# Magnetic-Imaging-Tile.net
KiCad netlist of a schematic drawn in EAGLE
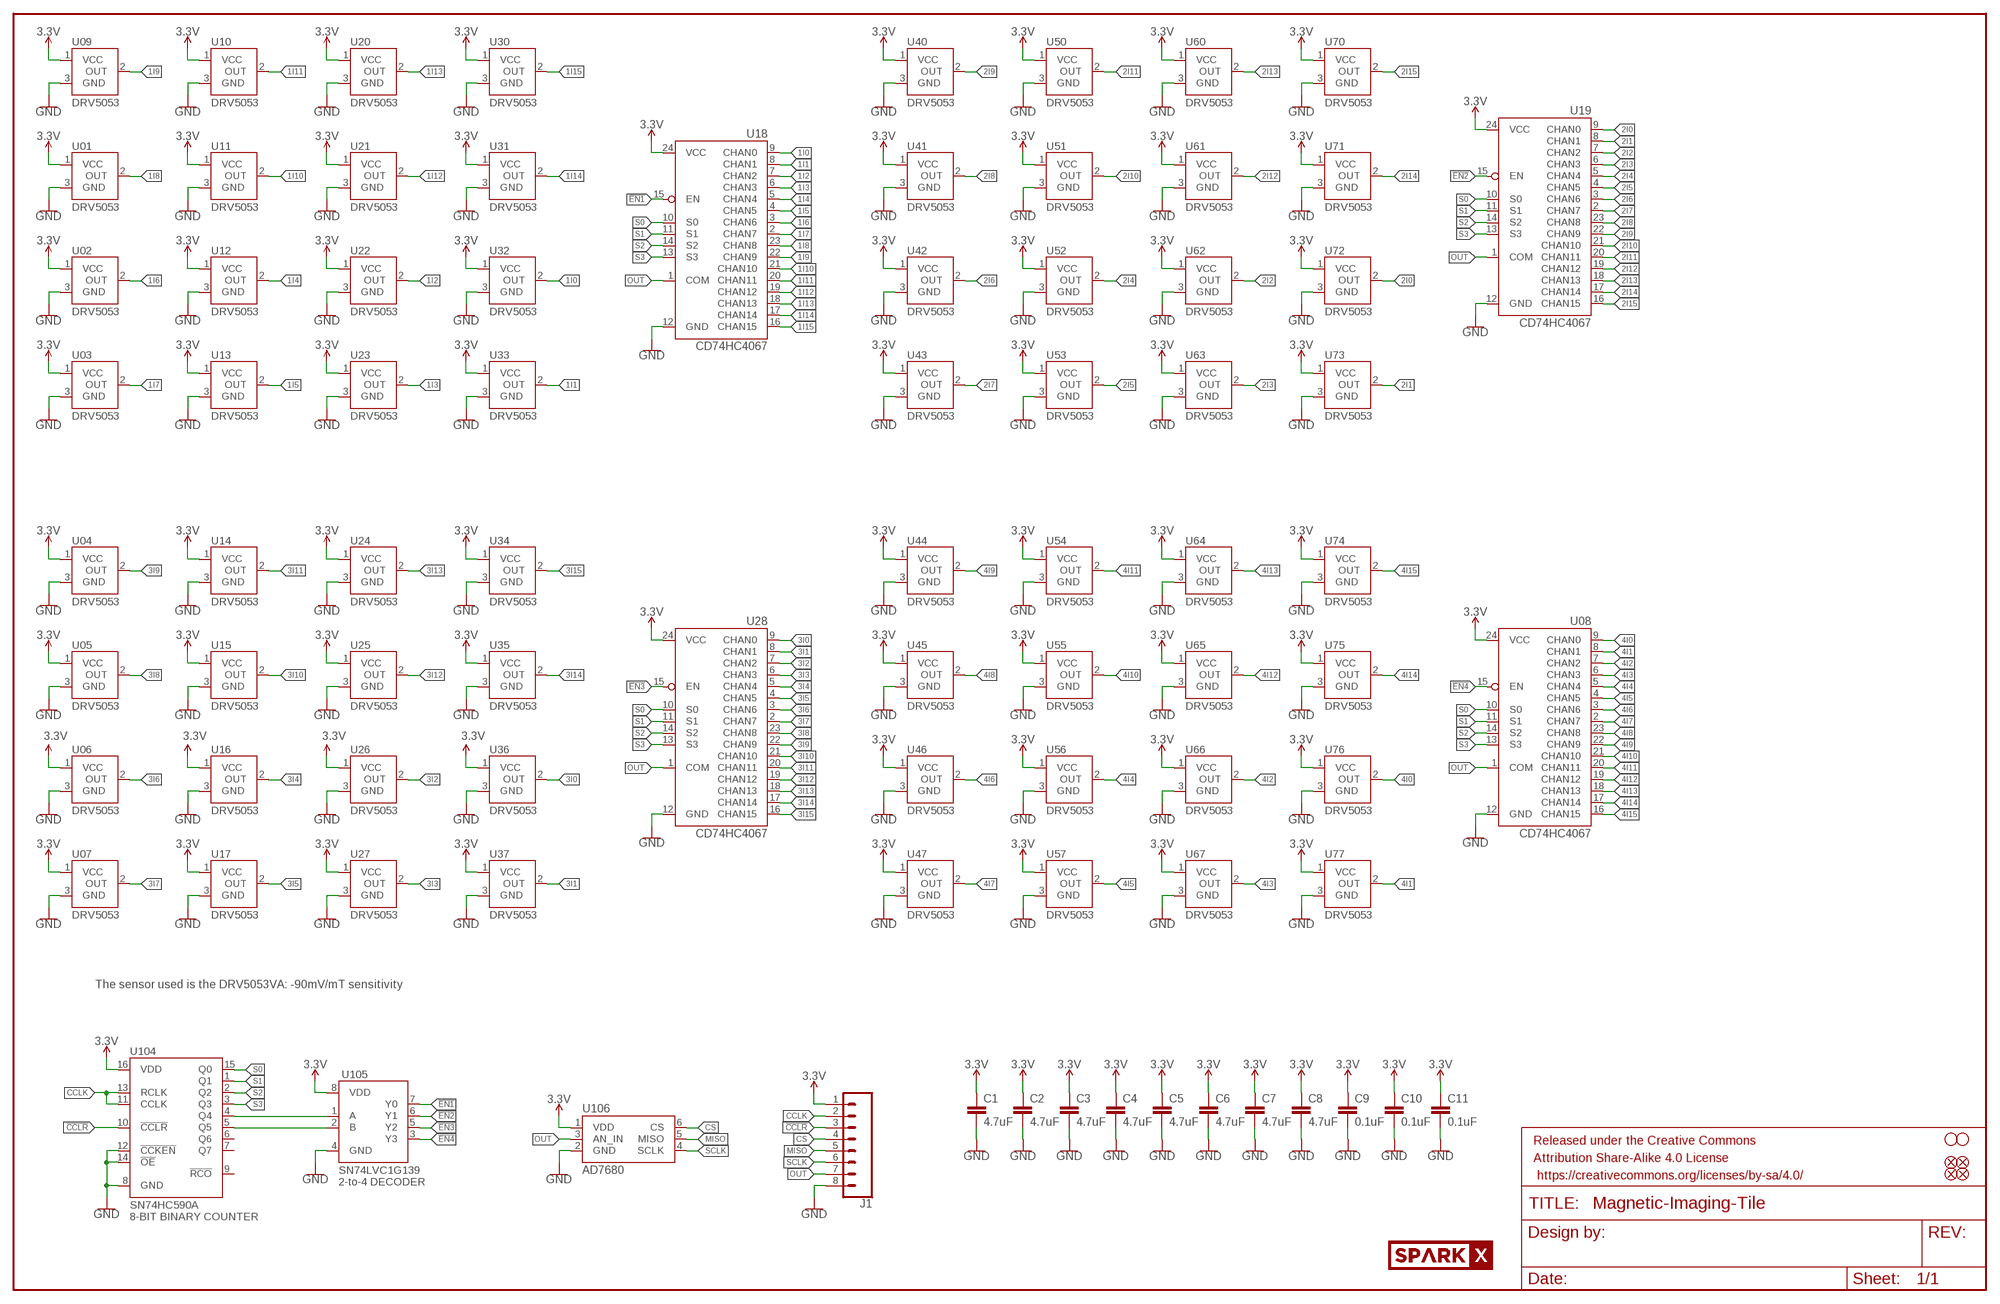
[diagram p0: schematic, sheet 1]

(export (version "E")
  (design (tool "Eeschema 10.0.6"))
  (components
    (comp (ref "C1")
      (value "4.7uF")
      (footprint "eagle-import:0603")
      (libsource (lib "eagle-import") (part "4.7UF-0603-6.3V-(10%)"))
    )
    (comp (ref "C2")
      (value "4.7uF")
      (footprint "eagle-import:0603")
      (libsource (lib "eagle-import") (part "4.7UF-0603-6.3V-(10%)"))
    )
    (comp (ref "C3")
      (value "4.7uF")
      (footprint "eagle-import:0603")
      (libsource (lib "eagle-import") (part "4.7UF-0603-6.3V-(10%)"))
    )
    (comp (ref "C4")
      (value "4.7uF")
      (footprint "eagle-import:0603")
      (libsource (lib "eagle-import") (part "4.7UF-0603-6.3V-(10%)"))
    )
    (comp (ref "C5")
      (value "4.7uF")
      (footprint "eagle-import:0603")
      (libsource (lib "eagle-import") (part "4.7UF-0603-6.3V-(10%)"))
    )
    (comp (ref "C6")
      (value "4.7uF")
      (footprint "eagle-import:0603")
      (libsource (lib "eagle-import") (part "4.7UF-0603-6.3V-(10%)"))
    )
    (comp (ref "C7")
      (value "4.7uF")
      (footprint "eagle-import:0603")
      (libsource (lib "eagle-import") (part "4.7UF-0603-6.3V-(10%)"))
    )
    (comp (ref "C8")
      (value "4.7uF")
      (footprint "eagle-import:0603")
      (libsource (lib "eagle-import") (part "4.7UF-0603-6.3V-(10%)"))
    )
    (comp (ref "C9")
      (value "0.1uF")
      (footprint "eagle-import:0603")
      (libsource (lib "eagle-import") (part "0.1UF-0603-25V-(+80/-20%)"))
    )
    (comp (ref "C10")
      (value "0.1uF")
      (footprint "eagle-import:0603")
      (libsource (lib "eagle-import") (part "0.1UF-0603-25V-(+80/-20%)"))
    )
    (comp (ref "C11")
      (value "0.1uF")
      (footprint "eagle-import:0603")
      (libsource (lib "eagle-import") (part "0.1UF-0603-25V-(+80/-20%)"))
    )
    (comp (ref "FD1")
      (value "FIDUCIALUFIDUCIAL")
      (footprint "eagle-import:FIDUCIAL-MICRO")
      (libsource (lib "eagle-import") (part "FIDUCIALUFIDUCIAL"))
    )
    (comp (ref "FD2")
      (value "FIDUCIALUFIDUCIAL")
      (footprint "eagle-import:FIDUCIAL-MICRO")
      (libsource (lib "eagle-import") (part "FIDUCIALUFIDUCIAL"))
    )
    (comp (ref "FD3")
      (value "FIDUCIALUFIDUCIAL")
      (footprint "eagle-import:FIDUCIAL-MICRO")
      (libsource (lib "eagle-import") (part "FIDUCIALUFIDUCIAL"))
    )
    (comp (ref "FD4")
      (value "FIDUCIALUFIDUCIAL")
      (footprint "eagle-import:FIDUCIAL-MICRO")
      (libsource (lib "eagle-import") (part "FIDUCIALUFIDUCIAL"))
    )
    (comp (ref "FRAME1")
      (value "FRAME-LEDGER")
      (footprint "eagle-import:CREATIVE_COMMONS")
      (libsource (lib "eagle-import") (part "FRAME-LEDGER"))
    )
    (comp (ref "H1")
      (value "STAND-OFF")
      (footprint "eagle-import:STAND-OFF")
      (libsource (lib "eagle-import") (part "STAND-OFF"))
    )
    (comp (ref "H2")
      (value "STAND-OFF")
      (footprint "eagle-import:STAND-OFF")
      (libsource (lib "eagle-import") (part "STAND-OFF"))
    )
    (comp (ref "J1")
      (value "CONN_08LOCK_NO_SILK")
      (footprint "eagle-import:1X08_LOCK_NO_SILK")
      (libsource (lib "eagle-import") (part "CONN_08LOCK_NO_SILK"))
    )
    (comp (ref "U$1")
      (value "SPARKX-LOGO3")
      (footprint "eagle-import:SPARKX-SMALL")
      (libsource (lib "eagle-import") (part "SPARKX-LOGO3"))
    )
    (comp (ref "U01")
      (value "DRV5053")
      (footprint "eagle-import:SOT23-3")
      (libsource (lib "eagle-import") (part "DRV5053"))
    )
    (comp (ref "U02")
      (value "DRV5053")
      (footprint "eagle-import:SOT23-3")
      (libsource (lib "eagle-import") (part "DRV5053"))
    )
    (comp (ref "U03")
      (value "DRV5053")
      (footprint "eagle-import:SOT23-3")
      (libsource (lib "eagle-import") (part "DRV5053"))
    )
    (comp (ref "U04")
      (value "DRV5053")
      (footprint "eagle-import:SOT23-3")
      (libsource (lib "eagle-import") (part "DRV5053"))
    )
    (comp (ref "U05")
      (value "DRV5053")
      (footprint "eagle-import:SOT23-3")
      (libsource (lib "eagle-import") (part "DRV5053"))
    )
    (comp (ref "U06")
      (value "DRV5053")
      (footprint "eagle-import:SOT23-3")
      (libsource (lib "eagle-import") (part "DRV5053"))
    )
    (comp (ref "U07")
      (value "DRV5053")
      (footprint "eagle-import:SOT23-3")
      (libsource (lib "eagle-import") (part "DRV5053"))
    )
    (comp (ref "U08")
      (value "CD74HC4067")
      (footprint "eagle-import:SSOP24")
      (libsource (lib "eagle-import") (part "744067SM96HC"))
    )
    (comp (ref "U09")
      (value "DRV5053")
      (footprint "eagle-import:SOT23-3")
      (libsource (lib "eagle-import") (part "DRV5053"))
    )
    (comp (ref "U10")
      (value "DRV5053")
      (footprint "eagle-import:SOT23-3")
      (libsource (lib "eagle-import") (part "DRV5053"))
    )
    (comp (ref "U11")
      (value "DRV5053")
      (footprint "eagle-import:SOT23-3")
      (libsource (lib "eagle-import") (part "DRV5053"))
    )
    (comp (ref "U12")
      (value "DRV5053")
      (footprint "eagle-import:SOT23-3")
      (libsource (lib "eagle-import") (part "DRV5053"))
    )
    (comp (ref "U13")
      (value "DRV5053")
      (footprint "eagle-import:SOT23-3")
      (libsource (lib "eagle-import") (part "DRV5053"))
    )
    (comp (ref "U14")
      (value "DRV5053")
      (footprint "eagle-import:SOT23-3")
      (libsource (lib "eagle-import") (part "DRV5053"))
    )
    (comp (ref "U15")
      (value "DRV5053")
      (footprint "eagle-import:SOT23-3")
      (libsource (lib "eagle-import") (part "DRV5053"))
    )
    (comp (ref "U16")
      (value "DRV5053")
      (footprint "eagle-import:SOT23-3")
      (libsource (lib "eagle-import") (part "DRV5053"))
    )
    (comp (ref "U17")
      (value "DRV5053")
      (footprint "eagle-import:SOT23-3")
      (libsource (lib "eagle-import") (part "DRV5053"))
    )
    (comp (ref "U18")
      (value "CD74HC4067")
      (footprint "eagle-import:SSOP24")
      (libsource (lib "eagle-import") (part "744067SM96HC"))
    )
    (comp (ref "U19")
      (value "CD74HC4067")
      (footprint "eagle-import:SSOP24")
      (libsource (lib "eagle-import") (part "744067SM96HC"))
    )
    (comp (ref "U20")
      (value "DRV5053")
      (footprint "eagle-import:SOT23-3")
      (libsource (lib "eagle-import") (part "DRV5053"))
    )
    (comp (ref "U21")
      (value "DRV5053")
      (footprint "eagle-import:SOT23-3")
      (libsource (lib "eagle-import") (part "DRV5053"))
    )
    (comp (ref "U22")
      (value "DRV5053")
      (footprint "eagle-import:SOT23-3")
      (libsource (lib "eagle-import") (part "DRV5053"))
    )
    (comp (ref "U23")
      (value "DRV5053")
      (footprint "eagle-import:SOT23-3")
      (libsource (lib "eagle-import") (part "DRV5053"))
    )
    (comp (ref "U24")
      (value "DRV5053")
      (footprint "eagle-import:SOT23-3")
      (libsource (lib "eagle-import") (part "DRV5053"))
    )
    (comp (ref "U25")
      (value "DRV5053")
      (footprint "eagle-import:SOT23-3")
      (libsource (lib "eagle-import") (part "DRV5053"))
    )
    (comp (ref "U26")
      (value "DRV5053")
      (footprint "eagle-import:SOT23-3")
      (libsource (lib "eagle-import") (part "DRV5053"))
    )
    (comp (ref "U27")
      (value "DRV5053")
      (footprint "eagle-import:SOT23-3")
      (libsource (lib "eagle-import") (part "DRV5053"))
    )
    (comp (ref "U28")
      (value "CD74HC4067")
      (footprint "eagle-import:SSOP24")
      (libsource (lib "eagle-import") (part "744067SM96HC"))
    )
    (comp (ref "U30")
      (value "DRV5053")
      (footprint "eagle-import:SOT23-3")
      (libsource (lib "eagle-import") (part "DRV5053"))
    )
    (comp (ref "U31")
      (value "DRV5053")
      (footprint "eagle-import:SOT23-3")
      (libsource (lib "eagle-import") (part "DRV5053"))
    )
    (comp (ref "U32")
      (value "DRV5053")
      (footprint "eagle-import:SOT23-3")
      (libsource (lib "eagle-import") (part "DRV5053"))
    )
    (comp (ref "U33")
      (value "DRV5053")
      (footprint "eagle-import:SOT23-3")
      (libsource (lib "eagle-import") (part "DRV5053"))
    )
    (comp (ref "U34")
      (value "DRV5053")
      (footprint "eagle-import:SOT23-3")
      (libsource (lib "eagle-import") (part "DRV5053"))
    )
    (comp (ref "U35")
      (value "DRV5053")
      (footprint "eagle-import:SOT23-3")
      (libsource (lib "eagle-import") (part "DRV5053"))
    )
    (comp (ref "U36")
      (value "DRV5053")
      (footprint "eagle-import:SOT23-3")
      (libsource (lib "eagle-import") (part "DRV5053"))
    )
    (comp (ref "U37")
      (value "DRV5053")
      (footprint "eagle-import:SOT23-3")
      (libsource (lib "eagle-import") (part "DRV5053"))
    )
    (comp (ref "U40")
      (value "DRV5053")
      (footprint "eagle-import:SOT23-3")
      (libsource (lib "eagle-import") (part "DRV5053"))
    )
    (comp (ref "U41")
      (value "DRV5053")
      (footprint "eagle-import:SOT23-3")
      (libsource (lib "eagle-import") (part "DRV5053"))
    )
    (comp (ref "U42")
      (value "DRV5053")
      (footprint "eagle-import:SOT23-3")
      (libsource (lib "eagle-import") (part "DRV5053"))
    )
    (comp (ref "U43")
      (value "DRV5053")
      (footprint "eagle-import:SOT23-3")
      (libsource (lib "eagle-import") (part "DRV5053"))
    )
    (comp (ref "U44")
      (value "DRV5053")
      (footprint "eagle-import:SOT23-3")
      (libsource (lib "eagle-import") (part "DRV5053"))
    )
    (comp (ref "U45")
      (value "DRV5053")
      (footprint "eagle-import:SOT23-3")
      (libsource (lib "eagle-import") (part "DRV5053"))
    )
    (comp (ref "U46")
      (value "DRV5053")
      (footprint "eagle-import:SOT23-3")
      (libsource (lib "eagle-import") (part "DRV5053"))
    )
    (comp (ref "U47")
      (value "DRV5053")
      (footprint "eagle-import:SOT23-3")
      (libsource (lib "eagle-import") (part "DRV5053"))
    )
    (comp (ref "U50")
      (value "DRV5053")
      (footprint "eagle-import:SOT23-3")
      (libsource (lib "eagle-import") (part "DRV5053"))
    )
    (comp (ref "U51")
      (value "DRV5053")
      (footprint "eagle-import:SOT23-3")
      (libsource (lib "eagle-import") (part "DRV5053"))
    )
    (comp (ref "U52")
      (value "DRV5053")
      (footprint "eagle-import:SOT23-3")
      (libsource (lib "eagle-import") (part "DRV5053"))
    )
    (comp (ref "U53")
      (value "DRV5053")
      (footprint "eagle-import:SOT23-3")
      (libsource (lib "eagle-import") (part "DRV5053"))
    )
    (comp (ref "U54")
      (value "DRV5053")
      (footprint "eagle-import:SOT23-3")
      (libsource (lib "eagle-import") (part "DRV5053"))
    )
    (comp (ref "U55")
      (value "DRV5053")
      (footprint "eagle-import:SOT23-3")
      (libsource (lib "eagle-import") (part "DRV5053"))
    )
    (comp (ref "U56")
      (value "DRV5053")
      (footprint "eagle-import:SOT23-3")
      (libsource (lib "eagle-import") (part "DRV5053"))
    )
    (comp (ref "U57")
      (value "DRV5053")
      (footprint "eagle-import:SOT23-3")
      (libsource (lib "eagle-import") (part "DRV5053"))
    )
    (comp (ref "U60")
      (value "DRV5053")
      (footprint "eagle-import:SOT23-3")
      (libsource (lib "eagle-import") (part "DRV5053"))
    )
    (comp (ref "U61")
      (value "DRV5053")
      (footprint "eagle-import:SOT23-3")
      (libsource (lib "eagle-import") (part "DRV5053"))
    )
    (comp (ref "U62")
      (value "DRV5053")
      (footprint "eagle-import:SOT23-3")
      (libsource (lib "eagle-import") (part "DRV5053"))
    )
    (comp (ref "U63")
      (value "DRV5053")
      (footprint "eagle-import:SOT23-3")
      (libsource (lib "eagle-import") (part "DRV5053"))
    )
    (comp (ref "U64")
      (value "DRV5053")
      (footprint "eagle-import:SOT23-3")
      (libsource (lib "eagle-import") (part "DRV5053"))
    )
    (comp (ref "U65")
      (value "DRV5053")
      (footprint "eagle-import:SOT23-3")
      (libsource (lib "eagle-import") (part "DRV5053"))
    )
    (comp (ref "U66")
      (value "DRV5053")
      (footprint "eagle-import:SOT23-3")
      (libsource (lib "eagle-import") (part "DRV5053"))
    )
    (comp (ref "U67")
      (value "DRV5053")
      (footprint "eagle-import:SOT23-3")
      (libsource (lib "eagle-import") (part "DRV5053"))
    )
    (comp (ref "U70")
      (value "DRV5053")
      (footprint "eagle-import:SOT23-3")
      (libsource (lib "eagle-import") (part "DRV5053"))
    )
    (comp (ref "U71")
      (value "DRV5053")
      (footprint "eagle-import:SOT23-3")
      (libsource (lib "eagle-import") (part "DRV5053"))
    )
    (comp (ref "U72")
      (value "DRV5053")
      (footprint "eagle-import:SOT23-3")
      (libsource (lib "eagle-import") (part "DRV5053"))
    )
    (comp (ref "U73")
      (value "DRV5053")
      (footprint "eagle-import:SOT23-3")
      (libsource (lib "eagle-import") (part "DRV5053"))
    )
    (comp (ref "U74")
      (value "DRV5053")
      (footprint "eagle-import:SOT23-3")
      (libsource (lib "eagle-import") (part "DRV5053"))
    )
    (comp (ref "U75")
      (value "DRV5053")
      (footprint "eagle-import:SOT23-3")
      (libsource (lib "eagle-import") (part "DRV5053"))
    )
    (comp (ref "U76")
      (value "DRV5053")
      (footprint "eagle-import:SOT23-3")
      (libsource (lib "eagle-import") (part "DRV5053"))
    )
    (comp (ref "U77")
      (value "DRV5053")
      (footprint "eagle-import:SOT23-3")
      (libsource (lib "eagle-import") (part "DRV5053"))
    )
    (comp (ref "U104")
      (value "SN74HC590A")
      (footprint "eagle-import:SO16")
      (libsource (lib "eagle-import") (part "SN74HC590A"))
    )
    (comp (ref "U105")
      (value "SN74LVC1G139")
      (footprint "eagle-import:SM8")
      (libsource (lib "eagle-import") (part "SN74LVC1G139"))
    )
    (comp (ref "U106")
      (value "AD7680")
      (footprint "eagle-import:SOT23-6")
      (libsource (lib "eagle-import") (part "AD7940"))
    )
  )
  (nets
    (net (code "1") (name "/~{CCLR}") (class "Default")
      (node (ref "J1") (pin "3") (pinfunction "3_3") (pintype "passive"))
      (node (ref "U104") (pin "10") (pinfunction "~{CCLR}_10") (pintype "bidirectional"))
    )
    (net (code "2") (name "/~{EN1}") (class "Default")
      (node (ref "U105") (pin "7") (pinfunction "Y0_7") (pintype "bidirectional"))
      (node (ref "U18") (pin "15") (pinfunction "EN_15") (pintype "input"))
    )
    (net (code "3") (name "/~{EN2}") (class "Default")
      (node (ref "U105") (pin "6") (pinfunction "Y1_6") (pintype "bidirectional"))
      (node (ref "U19") (pin "15") (pinfunction "EN_15") (pintype "input"))
    )
    (net (code "4") (name "/~{EN3}") (class "Default")
      (node (ref "U105") (pin "5") (pinfunction "Y2_5") (pintype "bidirectional"))
      (node (ref "U28") (pin "15") (pinfunction "EN_15") (pintype "input"))
    )
    (net (code "5") (name "/~{EN4}") (class "Default")
      (node (ref "U08") (pin "15") (pinfunction "EN_15") (pintype "input"))
      (node (ref "U105") (pin "3") (pinfunction "Y3_3") (pintype "bidirectional"))
    )
    (net (code "6") (name "1I0") (class "Default")
      (node (ref "U18") (pin "9") (pinfunction "CHAN0_9") (pintype "bidirectional"))
      (node (ref "U32") (pin "2") (pinfunction "OUT_2") (pintype "bidirectional"))
    )
    (net (code "7") (name "1I1") (class "Default")
      (node (ref "U18") (pin "8") (pinfunction "CHAN1_8") (pintype "bidirectional"))
      (node (ref "U33") (pin "2") (pinfunction "OUT_2") (pintype "bidirectional"))
    )
    (net (code "8") (name "1I2") (class "Default")
      (node (ref "U18") (pin "7") (pinfunction "CHAN2_7") (pintype "bidirectional"))
      (node (ref "U22") (pin "2") (pinfunction "OUT_2") (pintype "bidirectional"))
    )
    (net (code "9") (name "1I3") (class "Default")
      (node (ref "U18") (pin "6") (pinfunction "CHAN3_6") (pintype "bidirectional"))
      (node (ref "U23") (pin "2") (pinfunction "OUT_2") (pintype "bidirectional"))
    )
    (net (code "10") (name "1I4") (class "Default")
      (node (ref "U12") (pin "2") (pinfunction "OUT_2") (pintype "bidirectional"))
      (node (ref "U18") (pin "5") (pinfunction "CHAN4_5") (pintype "bidirectional"))
    )
    (net (code "11") (name "1I5") (class "Default")
      (node (ref "U13") (pin "2") (pinfunction "OUT_2") (pintype "bidirectional"))
      (node (ref "U18") (pin "4") (pinfunction "CHAN5_4") (pintype "bidirectional"))
    )
    (net (code "12") (name "1I6") (class "Default")
      (node (ref "U02") (pin "2") (pinfunction "OUT_2") (pintype "bidirectional"))
      (node (ref "U18") (pin "3") (pinfunction "CHAN6_3") (pintype "bidirectional"))
    )
    (net (code "13") (name "1I7") (class "Default")
      (node (ref "U03") (pin "2") (pinfunction "OUT_2") (pintype "bidirectional"))
      (node (ref "U18") (pin "2") (pinfunction "CHAN7_2") (pintype "bidirectional"))
    )
    (net (code "14") (name "1I8") (class "Default")
      (node (ref "U01") (pin "2") (pinfunction "OUT_2") (pintype "bidirectional"))
      (node (ref "U18") (pin "23") (pinfunction "CHAN8_23") (pintype "bidirectional"))
    )
    (net (code "15") (name "1I9") (class "Default")
      (node (ref "U09") (pin "2") (pinfunction "OUT_2") (pintype "bidirectional"))
      (node (ref "U18") (pin "22") (pinfunction "CHAN9_22") (pintype "bidirectional"))
    )
    (net (code "16") (name "1I10") (class "Default")
      (node (ref "U11") (pin "2") (pinfunction "OUT_2") (pintype "bidirectional"))
      (node (ref "U18") (pin "21") (pinfunction "CHAN10_21") (pintype "bidirectional"))
    )
    (net (code "17") (name "1I11") (class "Default")
      (node (ref "U10") (pin "2") (pinfunction "OUT_2") (pintype "bidirectional"))
      (node (ref "U18") (pin "20") (pinfunction "CHAN11_20") (pintype "bidirectional"))
    )
    (net (code "18") (name "1I12") (class "Default")
      (node (ref "U18") (pin "19") (pinfunction "CHAN12_19") (pintype "bidirectional"))
      (node (ref "U21") (pin "2") (pinfunction "OUT_2") (pintype "bidirectional"))
    )
    (net (code "19") (name "1I13") (class "Default")
      (node (ref "U18") (pin "18") (pinfunction "CHAN13_18") (pintype "bidirectional"))
      (node (ref "U20") (pin "2") (pinfunction "OUT_2") (pintype "bidirectional"))
    )
    (net (code "20") (name "1I14") (class "Default")
      (node (ref "U18") (pin "17") (pinfunction "CHAN14_17") (pintype "bidirectional"))
      (node (ref "U31") (pin "2") (pinfunction "OUT_2") (pintype "bidirectional"))
    )
    (net (code "21") (name "1I15") (class "Default")
      (node (ref "U18") (pin "16") (pinfunction "CHAN15_16") (pintype "bidirectional"))
      (node (ref "U30") (pin "2") (pinfunction "OUT_2") (pintype "bidirectional"))
    )
    (net (code "22") (name "2I0") (class "Default")
      (node (ref "U19") (pin "9") (pinfunction "CHAN0_9") (pintype "bidirectional"))
      (node (ref "U72") (pin "2") (pinfunction "OUT_2") (pintype "bidirectional"))
    )
    (net (code "23") (name "2I1") (class "Default")
      (node (ref "U19") (pin "8") (pinfunction "CHAN1_8") (pintype "bidirectional"))
      (node (ref "U73") (pin "2") (pinfunction "OUT_2") (pintype "bidirectional"))
    )
    (net (code "24") (name "2I2") (class "Default")
      (node (ref "U19") (pin "7") (pinfunction "CHAN2_7") (pintype "bidirectional"))
      (node (ref "U62") (pin "2") (pinfunction "OUT_2") (pintype "bidirectional"))
    )
    (net (code "25") (name "2I3") (class "Default")
      (node (ref "U19") (pin "6") (pinfunction "CHAN3_6") (pintype "bidirectional"))
      (node (ref "U63") (pin "2") (pinfunction "OUT_2") (pintype "bidirectional"))
    )
    (net (code "26") (name "2I4") (class "Default")
      (node (ref "U19") (pin "5") (pinfunction "CHAN4_5") (pintype "bidirectional"))
      (node (ref "U52") (pin "2") (pinfunction "OUT_2") (pintype "bidirectional"))
    )
    (net (code "27") (name "2I5") (class "Default")
      (node (ref "U19") (pin "4") (pinfunction "CHAN5_4") (pintype "bidirectional"))
      (node (ref "U53") (pin "2") (pinfunction "OUT_2") (pintype "bidirectional"))
    )
    (net (code "28") (name "2I6") (class "Default")
      (node (ref "U19") (pin "3") (pinfunction "CHAN6_3") (pintype "bidirectional"))
      (node (ref "U42") (pin "2") (pinfunction "OUT_2") (pintype "bidirectional"))
    )
    (net (code "29") (name "2I7") (class "Default")
      (node (ref "U19") (pin "2") (pinfunction "CHAN7_2") (pintype "bidirectional"))
      (node (ref "U43") (pin "2") (pinfunction "OUT_2") (pintype "bidirectional"))
    )
    (net (code "30") (name "2I8") (class "Default")
      (node (ref "U19") (pin "23") (pinfunction "CHAN8_23") (pintype "bidirectional"))
      (node (ref "U41") (pin "2") (pinfunction "OUT_2") (pintype "bidirectional"))
    )
    (net (code "31") (name "2I9") (class "Default")
      (node (ref "U19") (pin "22") (pinfunction "CHAN9_22") (pintype "bidirectional"))
      (node (ref "U40") (pin "2") (pinfunction "OUT_2") (pintype "bidirectional"))
    )
    (net (code "32") (name "2I10") (class "Default")
      (node (ref "U19") (pin "21") (pinfunction "CHAN10_21") (pintype "bidirectional"))
      (node (ref "U51") (pin "2") (pinfunction "OUT_2") (pintype "bidirectional"))
    )
    (net (code "33") (name "2I11") (class "Default")
      (node (ref "U19") (pin "20") (pinfunction "CHAN11_20") (pintype "bidirectional"))
      (node (ref "U50") (pin "2") (pinfunction "OUT_2") (pintype "bidirectional"))
    )
    (net (code "34") (name "2I12") (class "Default")
      (node (ref "U19") (pin "19") (pinfunction "CHAN12_19") (pintype "bidirectional"))
      (node (ref "U61") (pin "2") (pinfunction "OUT_2") (pintype "bidirectional"))
    )
    (net (code "35") (name "2I13") (class "Default")
      (node (ref "U19") (pin "18") (pinfunction "CHAN13_18") (pintype "bidirectional"))
      (node (ref "U60") (pin "2") (pinfunction "OUT_2") (pintype "bidirectional"))
    )
    (net (code "36") (name "2I14") (class "Default")
      (node (ref "U19") (pin "17") (pinfunction "CHAN14_17") (pintype "bidirectional"))
      (node (ref "U71") (pin "2") (pinfunction "OUT_2") (pintype "bidirectional"))
    )
    (net (code "37") (name "2I15") (class "Default")
      (node (ref "U19") (pin "16") (pinfunction "CHAN15_16") (pintype "bidirectional"))
      (node (ref "U70") (pin "2") (pinfunction "OUT_2") (pintype "bidirectional"))
    )
    (net (code "38") (name "3.3V") (class "Default")
      (node (ref "C1") (pin "1") (pinfunction "1_1") (pintype "passive"))
      (node (ref "C10") (pin "1") (pinfunction "1_1") (pintype "passive"))
      (node (ref "C11") (pin "1") (pinfunction "1_1") (pintype "passive"))
      (node (ref "C2") (pin "1") (pinfunction "1_1") (pintype "passive"))
      (node (ref "C3") (pin "1") (pinfunction "1_1") (pintype "passive"))
      (node (ref "C4") (pin "1") (pinfunction "1_1") (pintype "passive"))
      (node (ref "C5") (pin "1") (pinfunction "1_1") (pintype "passive"))
      (node (ref "C6") (pin "1") (pinfunction "1_1") (pintype "passive"))
      (node (ref "C7") (pin "1") (pinfunction "1_1") (pintype "passive"))
      (node (ref "C8") (pin "1") (pinfunction "1_1") (pintype "passive"))
      (node (ref "C9") (pin "1") (pinfunction "1_1") (pintype "passive"))
      (node (ref "J1") (pin "1") (pinfunction "1_1") (pintype "passive"))
      (node (ref "U01") (pin "1") (pinfunction "VCC_1") (pintype "bidirectional"))
      (node (ref "U02") (pin "1") (pinfunction "VCC_1") (pintype "bidirectional"))
      (node (ref "U03") (pin "1") (pinfunction "VCC_1") (pintype "bidirectional"))
      (node (ref "U04") (pin "1") (pinfunction "VCC_1") (pintype "bidirectional"))
      (node (ref "U05") (pin "1") (pinfunction "VCC_1") (pintype "bidirectional"))
      (node (ref "U06") (pin "1") (pinfunction "VCC_1") (pintype "bidirectional"))
      (node (ref "U07") (pin "1") (pinfunction "VCC_1") (pintype "bidirectional"))
      (node (ref "U08") (pin "24") (pinfunction "VCC_24") (pintype "bidirectional"))
      (node (ref "U09") (pin "1") (pinfunction "VCC_1") (pintype "bidirectional"))
      (node (ref "U10") (pin "1") (pinfunction "VCC_1") (pintype "bidirectional"))
      (node (ref "U104") (pin "16") (pinfunction "VDD_16") (pintype "bidirectional"))
      (node (ref "U105") (pin "8") (pinfunction "VDD_8") (pintype "bidirectional"))
      (node (ref "U106") (pin "1") (pinfunction "VDD_1") (pintype "bidirectional"))
      (node (ref "U11") (pin "1") (pinfunction "VCC_1") (pintype "bidirectional"))
      (node (ref "U12") (pin "1") (pinfunction "VCC_1") (pintype "bidirectional"))
      (node (ref "U13") (pin "1") (pinfunction "VCC_1") (pintype "bidirectional"))
      (node (ref "U14") (pin "1") (pinfunction "VCC_1") (pintype "bidirectional"))
      (node (ref "U15") (pin "1") (pinfunction "VCC_1") (pintype "bidirectional"))
      (node (ref "U16") (pin "1") (pinfunction "VCC_1") (pintype "bidirectional"))
      (node (ref "U17") (pin "1") (pinfunction "VCC_1") (pintype "bidirectional"))
      (node (ref "U18") (pin "24") (pinfunction "VCC_24") (pintype "bidirectional"))
      (node (ref "U19") (pin "24") (pinfunction "VCC_24") (pintype "bidirectional"))
      (node (ref "U20") (pin "1") (pinfunction "VCC_1") (pintype "bidirectional"))
      (node (ref "U21") (pin "1") (pinfunction "VCC_1") (pintype "bidirectional"))
      (node (ref "U22") (pin "1") (pinfunction "VCC_1") (pintype "bidirectional"))
      (node (ref "U23") (pin "1") (pinfunction "VCC_1") (pintype "bidirectional"))
      (node (ref "U24") (pin "1") (pinfunction "VCC_1") (pintype "bidirectional"))
      (node (ref "U25") (pin "1") (pinfunction "VCC_1") (pintype "bidirectional"))
      (node (ref "U26") (pin "1") (pinfunction "VCC_1") (pintype "bidirectional"))
      (node (ref "U27") (pin "1") (pinfunction "VCC_1") (pintype "bidirectional"))
      (node (ref "U28") (pin "24") (pinfunction "VCC_24") (pintype "bidirectional"))
      (node (ref "U30") (pin "1") (pinfunction "VCC_1") (pintype "bidirectional"))
      (node (ref "U31") (pin "1") (pinfunction "VCC_1") (pintype "bidirectional"))
      (node (ref "U32") (pin "1") (pinfunction "VCC_1") (pintype "bidirectional"))
      (node (ref "U33") (pin "1") (pinfunction "VCC_1") (pintype "bidirectional"))
      (node (ref "U34") (pin "1") (pinfunction "VCC_1") (pintype "bidirectional"))
      (node (ref "U35") (pin "1") (pinfunction "VCC_1") (pintype "bidirectional"))
      (node (ref "U36") (pin "1") (pinfunction "VCC_1") (pintype "bidirectional"))
      (node (ref "U37") (pin "1") (pinfunction "VCC_1") (pintype "bidirectional"))
      (node (ref "U40") (pin "1") (pinfunction "VCC_1") (pintype "bidirectional"))
      (node (ref "U41") (pin "1") (pinfunction "VCC_1") (pintype "bidirectional"))
      (node (ref "U42") (pin "1") (pinfunction "VCC_1") (pintype "bidirectional"))
      (node (ref "U43") (pin "1") (pinfunction "VCC_1") (pintype "bidirectional"))
      (node (ref "U44") (pin "1") (pinfunction "VCC_1") (pintype "bidirectional"))
      (node (ref "U45") (pin "1") (pinfunction "VCC_1") (pintype "bidirectional"))
      (node (ref "U46") (pin "1") (pinfunction "VCC_1") (pintype "bidirectional"))
      (node (ref "U47") (pin "1") (pinfunction "VCC_1") (pintype "bidirectional"))
      (node (ref "U50") (pin "1") (pinfunction "VCC_1") (pintype "bidirectional"))
      (node (ref "U51") (pin "1") (pinfunction "VCC_1") (pintype "bidirectional"))
      (node (ref "U52") (pin "1") (pinfunction "VCC_1") (pintype "bidirectional"))
      (node (ref "U53") (pin "1") (pinfunction "VCC_1") (pintype "bidirectional"))
      (node (ref "U54") (pin "1") (pinfunction "VCC_1") (pintype "bidirectional"))
      (node (ref "U55") (pin "1") (pinfunction "VCC_1") (pintype "bidirectional"))
      (node (ref "U56") (pin "1") (pinfunction "VCC_1") (pintype "bidirectional"))
      (node (ref "U57") (pin "1") (pinfunction "VCC_1") (pintype "bidirectional"))
      (node (ref "U60") (pin "1") (pinfunction "VCC_1") (pintype "bidirectional"))
      (node (ref "U61") (pin "1") (pinfunction "VCC_1") (pintype "bidirectional"))
      (node (ref "U62") (pin "1") (pinfunction "VCC_1") (pintype "bidirectional"))
      (node (ref "U63") (pin "1") (pinfunction "VCC_1") (pintype "bidirectional"))
      (node (ref "U64") (pin "1") (pinfunction "VCC_1") (pintype "bidirectional"))
      (node (ref "U65") (pin "1") (pinfunction "VCC_1") (pintype "bidirectional"))
      (node (ref "U66") (pin "1") (pinfunction "VCC_1") (pintype "bidirectional"))
      (node (ref "U67") (pin "1") (pinfunction "VCC_1") (pintype "bidirectional"))
      (node (ref "U70") (pin "1") (pinfunction "VCC_1") (pintype "bidirectional"))
      (node (ref "U71") (pin "1") (pinfunction "VCC_1") (pintype "bidirectional"))
      (node (ref "U72") (pin "1") (pinfunction "VCC_1") (pintype "bidirectional"))
      (node (ref "U73") (pin "1") (pinfunction "VCC_1") (pintype "bidirectional"))
      (node (ref "U74") (pin "1") (pinfunction "VCC_1") (pintype "bidirectional"))
      (node (ref "U75") (pin "1") (pinfunction "VCC_1") (pintype "bidirectional"))
      (node (ref "U76") (pin "1") (pinfunction "VCC_1") (pintype "bidirectional"))
      (node (ref "U77") (pin "1") (pinfunction "VCC_1") (pintype "bidirectional"))
    )
    (net (code "39") (name "3I0") (class "Default")
      (node (ref "U28") (pin "9") (pinfunction "CHAN0_9") (pintype "bidirectional"))
      (node (ref "U36") (pin "2") (pinfunction "OUT_2") (pintype "bidirectional"))
    )
    (net (code "40") (name "3I1") (class "Default")
      (node (ref "U28") (pin "8") (pinfunction "CHAN1_8") (pintype "bidirectional"))
      (node (ref "U37") (pin "2") (pinfunction "OUT_2") (pintype "bidirectional"))
    )
    (net (code "41") (name "3I2") (class "Default")
      (node (ref "U26") (pin "2") (pinfunction "OUT_2") (pintype "bidirectional"))
      (node (ref "U28") (pin "7") (pinfunction "CHAN2_7") (pintype "bidirectional"))
    )
    (net (code "42") (name "3I3") (class "Default")
      (node (ref "U27") (pin "2") (pinfunction "OUT_2") (pintype "bidirectional"))
      (node (ref "U28") (pin "6") (pinfunction "CHAN3_6") (pintype "bidirectional"))
    )
    (net (code "43") (name "3I4") (class "Default")
      (node (ref "U16") (pin "2") (pinfunction "OUT_2") (pintype "bidirectional"))
      (node (ref "U28") (pin "5") (pinfunction "CHAN4_5") (pintype "bidirectional"))
    )
    (net (code "44") (name "3I5") (class "Default")
      (node (ref "U17") (pin "2") (pinfunction "OUT_2") (pintype "bidirectional"))
      (node (ref "U28") (pin "4") (pinfunction "CHAN5_4") (pintype "bidirectional"))
    )
    (net (code "45") (name "3I6") (class "Default")
      (node (ref "U06") (pin "2") (pinfunction "OUT_2") (pintype "bidirectional"))
      (node (ref "U28") (pin "3") (pinfunction "CHAN6_3") (pintype "bidirectional"))
    )
    (net (code "46") (name "3I7") (class "Default")
      (node (ref "U07") (pin "2") (pinfunction "OUT_2") (pintype "bidirectional"))
      (node (ref "U28") (pin "2") (pinfunction "CHAN7_2") (pintype "bidirectional"))
    )
    (net (code "47") (name "3I8") (class "Default")
      (node (ref "U05") (pin "2") (pinfunction "OUT_2") (pintype "bidirectional"))
      (node (ref "U28") (pin "23") (pinfunction "CHAN8_23") (pintype "bidirectional"))
    )
    (net (code "48") (name "3I9") (class "Default")
      (node (ref "U04") (pin "2") (pinfunction "OUT_2") (pintype "bidirectional"))
      (node (ref "U28") (pin "22") (pinfunction "CHAN9_22") (pintype "bidirectional"))
    )
    (net (code "49") (name "3I10") (class "Default")
      (node (ref "U15") (pin "2") (pinfunction "OUT_2") (pintype "bidirectional"))
      (node (ref "U28") (pin "21") (pinfunction "CHAN10_21") (pintype "bidirectional"))
    )
    (net (code "50") (name "3I11") (class "Default")
      (node (ref "U14") (pin "2") (pinfunction "OUT_2") (pintype "bidirectional"))
      (node (ref "U28") (pin "20") (pinfunction "CHAN11_20") (pintype "bidirectional"))
    )
    (net (code "51") (name "3I12") (class "Default")
      (node (ref "U25") (pin "2") (pinfunction "OUT_2") (pintype "bidirectional"))
      (node (ref "U28") (pin "19") (pinfunction "CHAN12_19") (pintype "bidirectional"))
    )
    (net (code "52") (name "3I13") (class "Default")
      (node (ref "U24") (pin "2") (pinfunction "OUT_2") (pintype "bidirectional"))
      (node (ref "U28") (pin "18") (pinfunction "CHAN13_18") (pintype "bidirectional"))
    )
    (net (code "53") (name "3I14") (class "Default")
      (node (ref "U28") (pin "17") (pinfunction "CHAN14_17") (pintype "bidirectional"))
      (node (ref "U35") (pin "2") (pinfunction "OUT_2") (pintype "bidirectional"))
    )
    (net (code "54") (name "3I15") (class "Default")
      (node (ref "U28") (pin "16") (pinfunction "CHAN15_16") (pintype "bidirectional"))
      (node (ref "U34") (pin "2") (pinfunction "OUT_2") (pintype "bidirectional"))
    )
    (net (code "55") (name "4I0") (class "Default")
      (node (ref "U08") (pin "9") (pinfunction "CHAN0_9") (pintype "bidirectional"))
      (node (ref "U76") (pin "2") (pinfunction "OUT_2") (pintype "bidirectional"))
    )
    (net (code "56") (name "4I1") (class "Default")
      (node (ref "U08") (pin "8") (pinfunction "CHAN1_8") (pintype "bidirectional"))
      (node (ref "U77") (pin "2") (pinfunction "OUT_2") (pintype "bidirectional"))
    )
    (net (code "57") (name "4I2") (class "Default")
      (node (ref "U08") (pin "7") (pinfunction "CHAN2_7") (pintype "bidirectional"))
      (node (ref "U66") (pin "2") (pinfunction "OUT_2") (pintype "bidirectional"))
    )
    (net (code "58") (name "4I3") (class "Default")
      (node (ref "U08") (pin "6") (pinfunction "CHAN3_6") (pintype "bidirectional"))
      (node (ref "U67") (pin "2") (pinfunction "OUT_2") (pintype "bidirectional"))
    )
    (net (code "59") (name "4I4") (class "Default")
      (node (ref "U08") (pin "5") (pinfunction "CHAN4_5") (pintype "bidirectional"))
      (node (ref "U56") (pin "2") (pinfunction "OUT_2") (pintype "bidirectional"))
    )
    (net (code "60") (name "4I5") (class "Default")
      (node (ref "U08") (pin "4") (pinfunction "CHAN5_4") (pintype "bidirectional"))
      (node (ref "U57") (pin "2") (pinfunction "OUT_2") (pintype "bidirectional"))
    )
    (net (code "61") (name "4I6") (class "Default")
      (node (ref "U08") (pin "3") (pinfunction "CHAN6_3") (pintype "bidirectional"))
      (node (ref "U46") (pin "2") (pinfunction "OUT_2") (pintype "bidirectional"))
    )
    (net (code "62") (name "4I7") (class "Default")
      (node (ref "U08") (pin "2") (pinfunction "CHAN7_2") (pintype "bidirectional"))
      (node (ref "U47") (pin "2") (pinfunction "OUT_2") (pintype "bidirectional"))
    )
    (net (code "63") (name "4I8") (class "Default")
      (node (ref "U08") (pin "23") (pinfunction "CHAN8_23") (pintype "bidirectional"))
      (node (ref "U45") (pin "2") (pinfunction "OUT_2") (pintype "bidirectional"))
    )
    (net (code "64") (name "4I9") (class "Default")
      (node (ref "U08") (pin "22") (pinfunction "CHAN9_22") (pintype "bidirectional"))
      (node (ref "U44") (pin "2") (pinfunction "OUT_2") (pintype "bidirectional"))
    )
    (net (code "65") (name "4I10") (class "Default")
      (node (ref "U08") (pin "21") (pinfunction "CHAN10_21") (pintype "bidirectional"))
      (node (ref "U55") (pin "2") (pinfunction "OUT_2") (pintype "bidirectional"))
    )
    (net (code "66") (name "4I11") (class "Default")
      (node (ref "U08") (pin "20") (pinfunction "CHAN11_20") (pintype "bidirectional"))
      (node (ref "U54") (pin "2") (pinfunction "OUT_2") (pintype "bidirectional"))
    )
    (net (code "67") (name "4I12") (class "Default")
      (node (ref "U08") (pin "19") (pinfunction "CHAN12_19") (pintype "bidirectional"))
      (node (ref "U65") (pin "2") (pinfunction "OUT_2") (pintype "bidirectional"))
    )
    (net (code "68") (name "4I13") (class "Default")
      (node (ref "U08") (pin "18") (pinfunction "CHAN13_18") (pintype "bidirectional"))
      (node (ref "U64") (pin "2") (pinfunction "OUT_2") (pintype "bidirectional"))
    )
    (net (code "69") (name "4I14") (class "Default")
      (node (ref "U08") (pin "17") (pinfunction "CHAN14_17") (pintype "bidirectional"))
      (node (ref "U75") (pin "2") (pinfunction "OUT_2") (pintype "bidirectional"))
    )
    (net (code "70") (name "4I15") (class "Default")
      (node (ref "U08") (pin "16") (pinfunction "CHAN15_16") (pintype "bidirectional"))
      (node (ref "U74") (pin "2") (pinfunction "OUT_2") (pintype "bidirectional"))
    )
    (net (code "71") (name "CCLK") (class "Default")
      (node (ref "J1") (pin "2") (pinfunction "2_2") (pintype "passive"))
      (node (ref "U104") (pin "11") (pinfunction "CCLK_11") (pintype "bidirectional"))
      (node (ref "U104") (pin "13") (pinfunction "RCLK_13") (pintype "bidirectional"))
    )
    (net (code "72") (name "CS") (class "Default")
      (node (ref "J1") (pin "4") (pinfunction "4_4") (pintype "passive"))
      (node (ref "U106") (pin "6") (pinfunction "CS_6") (pintype "bidirectional"))
    )
    (net (code "73") (name "GND") (class "Default")
      (node (ref "C1") (pin "2") (pinfunction "2_2") (pintype "passive"))
      (node (ref "C10") (pin "2") (pinfunction "2_2") (pintype "passive"))
      (node (ref "C11") (pin "2") (pinfunction "2_2") (pintype "passive"))
      (node (ref "C2") (pin "2") (pinfunction "2_2") (pintype "passive"))
      (node (ref "C3") (pin "2") (pinfunction "2_2") (pintype "passive"))
      (node (ref "C4") (pin "2") (pinfunction "2_2") (pintype "passive"))
      (node (ref "C5") (pin "2") (pinfunction "2_2") (pintype "passive"))
      (node (ref "C6") (pin "2") (pinfunction "2_2") (pintype "passive"))
      (node (ref "C7") (pin "2") (pinfunction "2_2") (pintype "passive"))
      (node (ref "C8") (pin "2") (pinfunction "2_2") (pintype "passive"))
      (node (ref "C9") (pin "2") (pinfunction "2_2") (pintype "passive"))
      (node (ref "J1") (pin "8") (pinfunction "8_8") (pintype "passive"))
      (node (ref "U01") (pin "3") (pinfunction "GND_3") (pintype "bidirectional"))
      (node (ref "U02") (pin "3") (pinfunction "GND_3") (pintype "bidirectional"))
      (node (ref "U03") (pin "3") (pinfunction "GND_3") (pintype "bidirectional"))
      (node (ref "U04") (pin "3") (pinfunction "GND_3") (pintype "bidirectional"))
      (node (ref "U05") (pin "3") (pinfunction "GND_3") (pintype "bidirectional"))
      (node (ref "U06") (pin "3") (pinfunction "GND_3") (pintype "bidirectional"))
      (node (ref "U07") (pin "3") (pinfunction "GND_3") (pintype "bidirectional"))
      (node (ref "U08") (pin "12") (pinfunction "GND_12") (pintype "bidirectional"))
      (node (ref "U09") (pin "3") (pinfunction "GND_3") (pintype "bidirectional"))
      (node (ref "U10") (pin "3") (pinfunction "GND_3") (pintype "bidirectional"))
      (node (ref "U104") (pin "12") (pinfunction "~{CCKEN}_12") (pintype "bidirectional"))
      (node (ref "U104") (pin "14") (pinfunction "~{OE}_14") (pintype "bidirectional"))
      (node (ref "U104") (pin "8") (pinfunction "GND_8") (pintype "bidirectional"))
      (node (ref "U105") (pin "4") (pinfunction "GND_4") (pintype "bidirectional"))
      (node (ref "U106") (pin "2") (pinfunction "GND_2") (pintype "bidirectional"))
      (node (ref "U11") (pin "3") (pinfunction "GND_3") (pintype "bidirectional"))
      (node (ref "U12") (pin "3") (pinfunction "GND_3") (pintype "bidirectional"))
      (node (ref "U13") (pin "3") (pinfunction "GND_3") (pintype "bidirectional"))
      (node (ref "U14") (pin "3") (pinfunction "GND_3") (pintype "bidirectional"))
      (node (ref "U15") (pin "3") (pinfunction "GND_3") (pintype "bidirectional"))
      (node (ref "U16") (pin "3") (pinfunction "GND_3") (pintype "bidirectional"))
      (node (ref "U17") (pin "3") (pinfunction "GND_3") (pintype "bidirectional"))
      (node (ref "U18") (pin "12") (pinfunction "GND_12") (pintype "bidirectional"))
      (node (ref "U19") (pin "12") (pinfunction "GND_12") (pintype "bidirectional"))
      (node (ref "U20") (pin "3") (pinfunction "GND_3") (pintype "bidirectional"))
      (node (ref "U21") (pin "3") (pinfunction "GND_3") (pintype "bidirectional"))
      (node (ref "U22") (pin "3") (pinfunction "GND_3") (pintype "bidirectional"))
      (node (ref "U23") (pin "3") (pinfunction "GND_3") (pintype "bidirectional"))
      (node (ref "U24") (pin "3") (pinfunction "GND_3") (pintype "bidirectional"))
      (node (ref "U25") (pin "3") (pinfunction "GND_3") (pintype "bidirectional"))
      (node (ref "U26") (pin "3") (pinfunction "GND_3") (pintype "bidirectional"))
      (node (ref "U27") (pin "3") (pinfunction "GND_3") (pintype "bidirectional"))
      (node (ref "U28") (pin "12") (pinfunction "GND_12") (pintype "bidirectional"))
      (node (ref "U30") (pin "3") (pinfunction "GND_3") (pintype "bidirectional"))
      (node (ref "U31") (pin "3") (pinfunction "GND_3") (pintype "bidirectional"))
      (node (ref "U32") (pin "3") (pinfunction "GND_3") (pintype "bidirectional"))
      (node (ref "U33") (pin "3") (pinfunction "GND_3") (pintype "bidirectional"))
      (node (ref "U34") (pin "3") (pinfunction "GND_3") (pintype "bidirectional"))
      (node (ref "U35") (pin "3") (pinfunction "GND_3") (pintype "bidirectional"))
      (node (ref "U36") (pin "3") (pinfunction "GND_3") (pintype "bidirectional"))
      (node (ref "U37") (pin "3") (pinfunction "GND_3") (pintype "bidirectional"))
      (node (ref "U40") (pin "3") (pinfunction "GND_3") (pintype "bidirectional"))
      (node (ref "U41") (pin "3") (pinfunction "GND_3") (pintype "bidirectional"))
      (node (ref "U42") (pin "3") (pinfunction "GND_3") (pintype "bidirectional"))
      (node (ref "U43") (pin "3") (pinfunction "GND_3") (pintype "bidirectional"))
      (node (ref "U44") (pin "3") (pinfunction "GND_3") (pintype "bidirectional"))
      (node (ref "U45") (pin "3") (pinfunction "GND_3") (pintype "bidirectional"))
      (node (ref "U46") (pin "3") (pinfunction "GND_3") (pintype "bidirectional"))
      (node (ref "U47") (pin "3") (pinfunction "GND_3") (pintype "bidirectional"))
      (node (ref "U50") (pin "3") (pinfunction "GND_3") (pintype "bidirectional"))
      (node (ref "U51") (pin "3") (pinfunction "GND_3") (pintype "bidirectional"))
      (node (ref "U52") (pin "3") (pinfunction "GND_3") (pintype "bidirectional"))
      (node (ref "U53") (pin "3") (pinfunction "GND_3") (pintype "bidirectional"))
      (node (ref "U54") (pin "3") (pinfunction "GND_3") (pintype "bidirectional"))
      (node (ref "U55") (pin "3") (pinfunction "GND_3") (pintype "bidirectional"))
      (node (ref "U56") (pin "3") (pinfunction "GND_3") (pintype "bidirectional"))
      (node (ref "U57") (pin "3") (pinfunction "GND_3") (pintype "bidirectional"))
      (node (ref "U60") (pin "3") (pinfunction "GND_3") (pintype "bidirectional"))
      (node (ref "U61") (pin "3") (pinfunction "GND_3") (pintype "bidirectional"))
      (node (ref "U62") (pin "3") (pinfunction "GND_3") (pintype "bidirectional"))
      (node (ref "U63") (pin "3") (pinfunction "GND_3") (pintype "bidirectional"))
      (node (ref "U64") (pin "3") (pinfunction "GND_3") (pintype "bidirectional"))
      (node (ref "U65") (pin "3") (pinfunction "GND_3") (pintype "bidirectional"))
      (node (ref "U66") (pin "3") (pinfunction "GND_3") (pintype "bidirectional"))
      (node (ref "U67") (pin "3") (pinfunction "GND_3") (pintype "bidirectional"))
      (node (ref "U70") (pin "3") (pinfunction "GND_3") (pintype "bidirectional"))
      (node (ref "U71") (pin "3") (pinfunction "GND_3") (pintype "bidirectional"))
      (node (ref "U72") (pin "3") (pinfunction "GND_3") (pintype "bidirectional"))
      (node (ref "U73") (pin "3") (pinfunction "GND_3") (pintype "bidirectional"))
      (node (ref "U74") (pin "3") (pinfunction "GND_3") (pintype "bidirectional"))
      (node (ref "U75") (pin "3") (pinfunction "GND_3") (pintype "bidirectional"))
      (node (ref "U76") (pin "3") (pinfunction "GND_3") (pintype "bidirectional"))
      (node (ref "U77") (pin "3") (pinfunction "GND_3") (pintype "bidirectional"))
    )
    (net (code "74") (name "MISO") (class "Default")
      (node (ref "J1") (pin "5") (pinfunction "5_5") (pintype "passive"))
      (node (ref "U106") (pin "5") (pinfunction "MISO_5") (pintype "bidirectional"))
    )
    (net (code "75") (name "Net-(U104-Q4)") (class "Default")
      (node (ref "U104") (pin "4") (pinfunction "Q4_4") (pintype "bidirectional"))
      (node (ref "U105") (pin "1") (pinfunction "A_1") (pintype "bidirectional"))
    )
    (net (code "76") (name "Net-(U104-Q5)") (class "Default")
      (node (ref "U104") (pin "5") (pinfunction "Q5_5") (pintype "bidirectional"))
      (node (ref "U105") (pin "2") (pinfunction "B_2") (pintype "bidirectional"))
    )
    (net (code "77") (name "OUT") (class "Default")
      (node (ref "J1") (pin "7") (pinfunction "7_7") (pintype "passive"))
      (node (ref "U08") (pin "1") (pinfunction "COM_1") (pintype "bidirectional"))
      (node (ref "U106") (pin "3") (pinfunction "AN_IN_3") (pintype "bidirectional"))
      (node (ref "U18") (pin "1") (pinfunction "COM_1") (pintype "bidirectional"))
      (node (ref "U19") (pin "1") (pinfunction "COM_1") (pintype "bidirectional"))
      (node (ref "U28") (pin "1") (pinfunction "COM_1") (pintype "bidirectional"))
    )
    (net (code "78") (name "S0") (class "Default")
      (node (ref "U08") (pin "10") (pinfunction "S0_10") (pintype "input"))
      (node (ref "U104") (pin "15") (pinfunction "Q0_15") (pintype "bidirectional"))
      (node (ref "U18") (pin "10") (pinfunction "S0_10") (pintype "input"))
      (node (ref "U19") (pin "10") (pinfunction "S0_10") (pintype "input"))
      (node (ref "U28") (pin "10") (pinfunction "S0_10") (pintype "input"))
    )
    (net (code "79") (name "S1") (class "Default")
      (node (ref "U08") (pin "11") (pinfunction "S1_11") (pintype "input"))
      (node (ref "U104") (pin "1") (pinfunction "Q1_1") (pintype "bidirectional"))
      (node (ref "U18") (pin "11") (pinfunction "S1_11") (pintype "input"))
      (node (ref "U19") (pin "11") (pinfunction "S1_11") (pintype "input"))
      (node (ref "U28") (pin "11") (pinfunction "S1_11") (pintype "input"))
    )
    (net (code "80") (name "S2") (class "Default")
      (node (ref "U08") (pin "14") (pinfunction "S2_14") (pintype "input"))
      (node (ref "U104") (pin "2") (pinfunction "Q2_2") (pintype "bidirectional"))
      (node (ref "U18") (pin "14") (pinfunction "S2_14") (pintype "input"))
      (node (ref "U19") (pin "14") (pinfunction "S2_14") (pintype "input"))
      (node (ref "U28") (pin "14") (pinfunction "S2_14") (pintype "input"))
    )
    (net (code "81") (name "S3") (class "Default")
      (node (ref "U08") (pin "13") (pinfunction "S3_13") (pintype "input"))
      (node (ref "U104") (pin "3") (pinfunction "Q3_3") (pintype "bidirectional"))
      (node (ref "U18") (pin "13") (pinfunction "S3_13") (pintype "input"))
      (node (ref "U19") (pin "13") (pinfunction "S3_13") (pintype "input"))
      (node (ref "U28") (pin "13") (pinfunction "S3_13") (pintype "input"))
    )
    (net (code "82") (name "SCLK") (class "Default")
      (node (ref "J1") (pin "6") (pinfunction "6_6") (pintype "passive"))
      (node (ref "U106") (pin "4") (pinfunction "SCLK_4") (pintype "bidirectional"))
    )
    (net (code "83") (name "unconnected-(U104-Q6-Pad6)") (class "Default")
      (node (ref "U104") (pin "6") (pinfunction "Q6_6") (pintype "bidirectional"))
    )
    (net (code "84") (name "unconnected-(U104-Q7-Pad7)") (class "Default")
      (node (ref "U104") (pin "7") (pinfunction "Q7_7") (pintype "bidirectional"))
    )
    (net (code "85") (name "unconnected-(U104-~{RCO}-Pad9)") (class "Default")
      (node (ref "U104") (pin "9") (pinfunction "~{RCO}_9") (pintype "bidirectional"))
    )
  )
)
